# Sheet1.net
KiCad netlist of a schematic drawn in Altium Designer
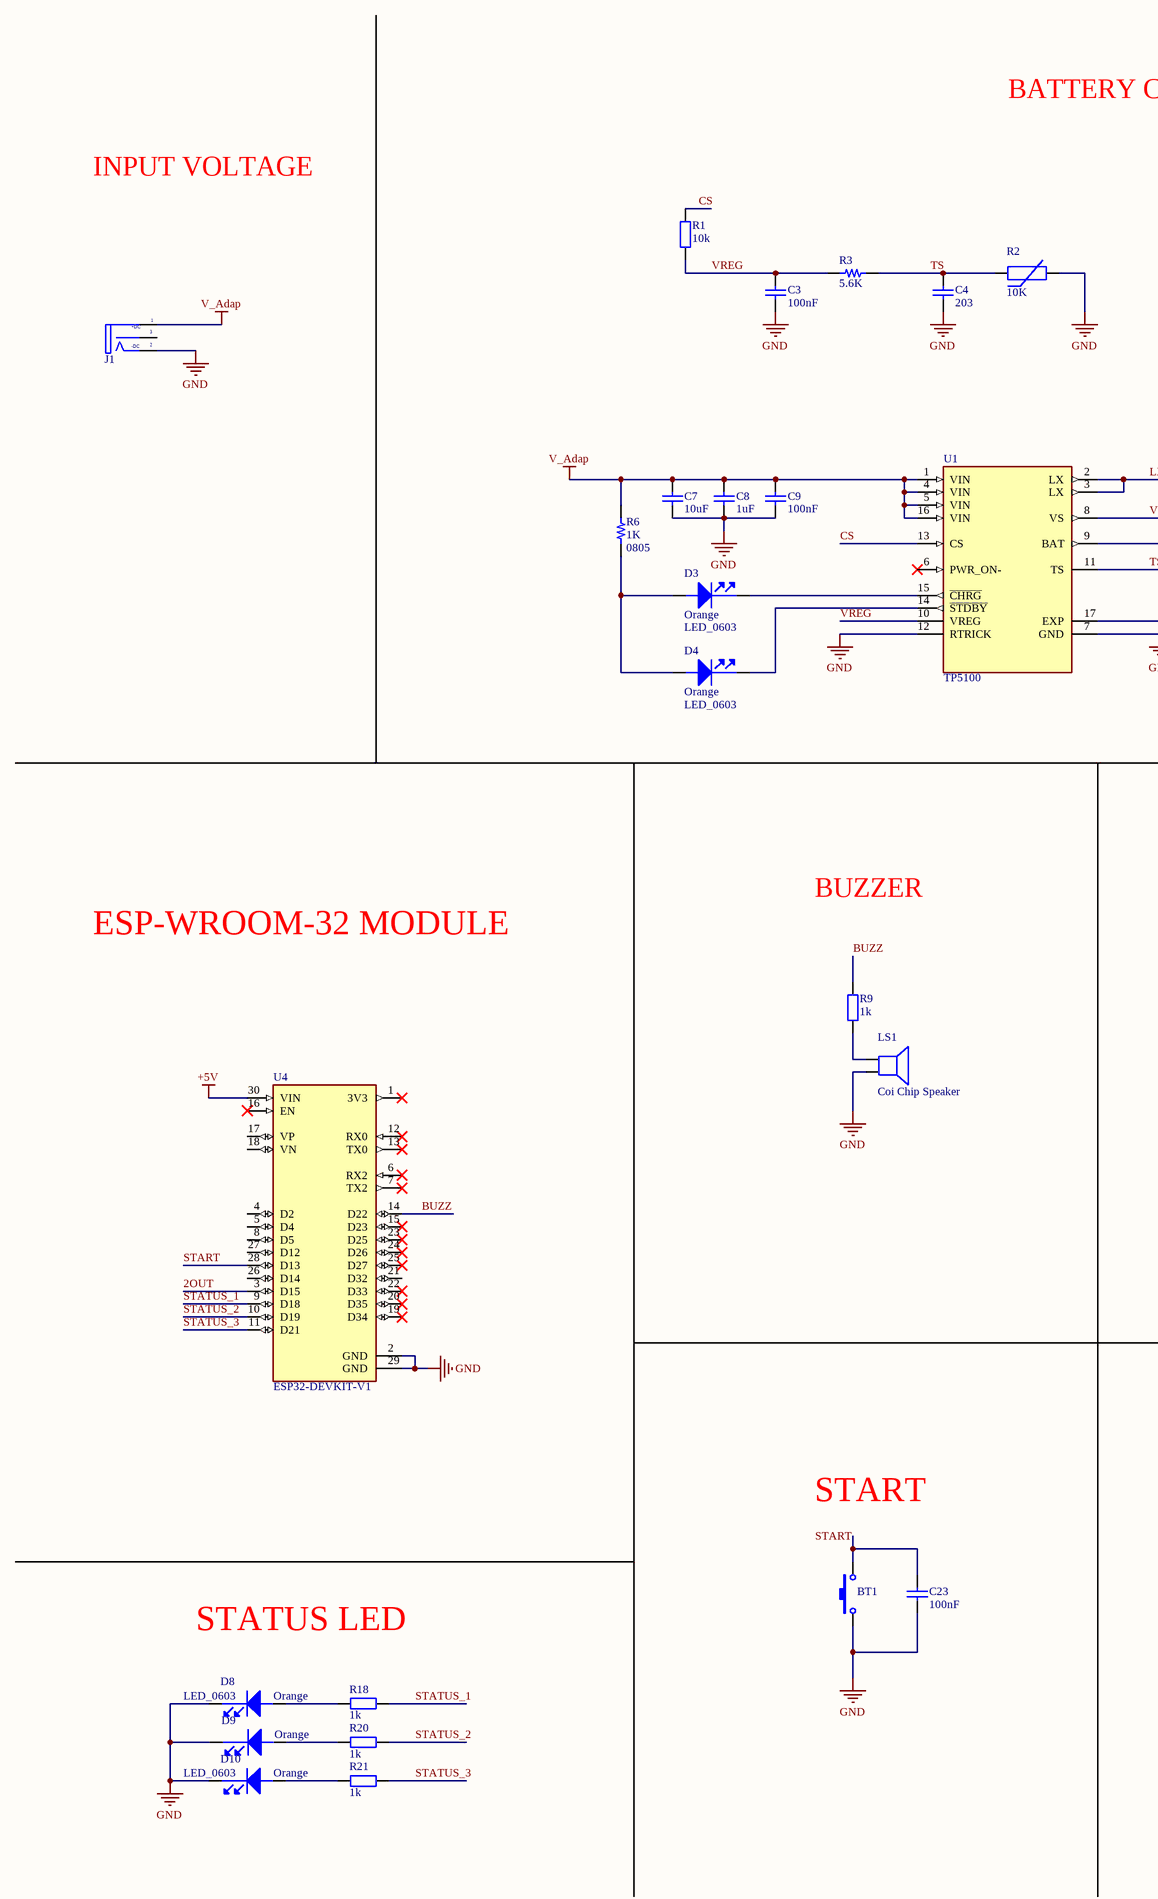
[diagram p0: Sheet1.SchDoc, left]
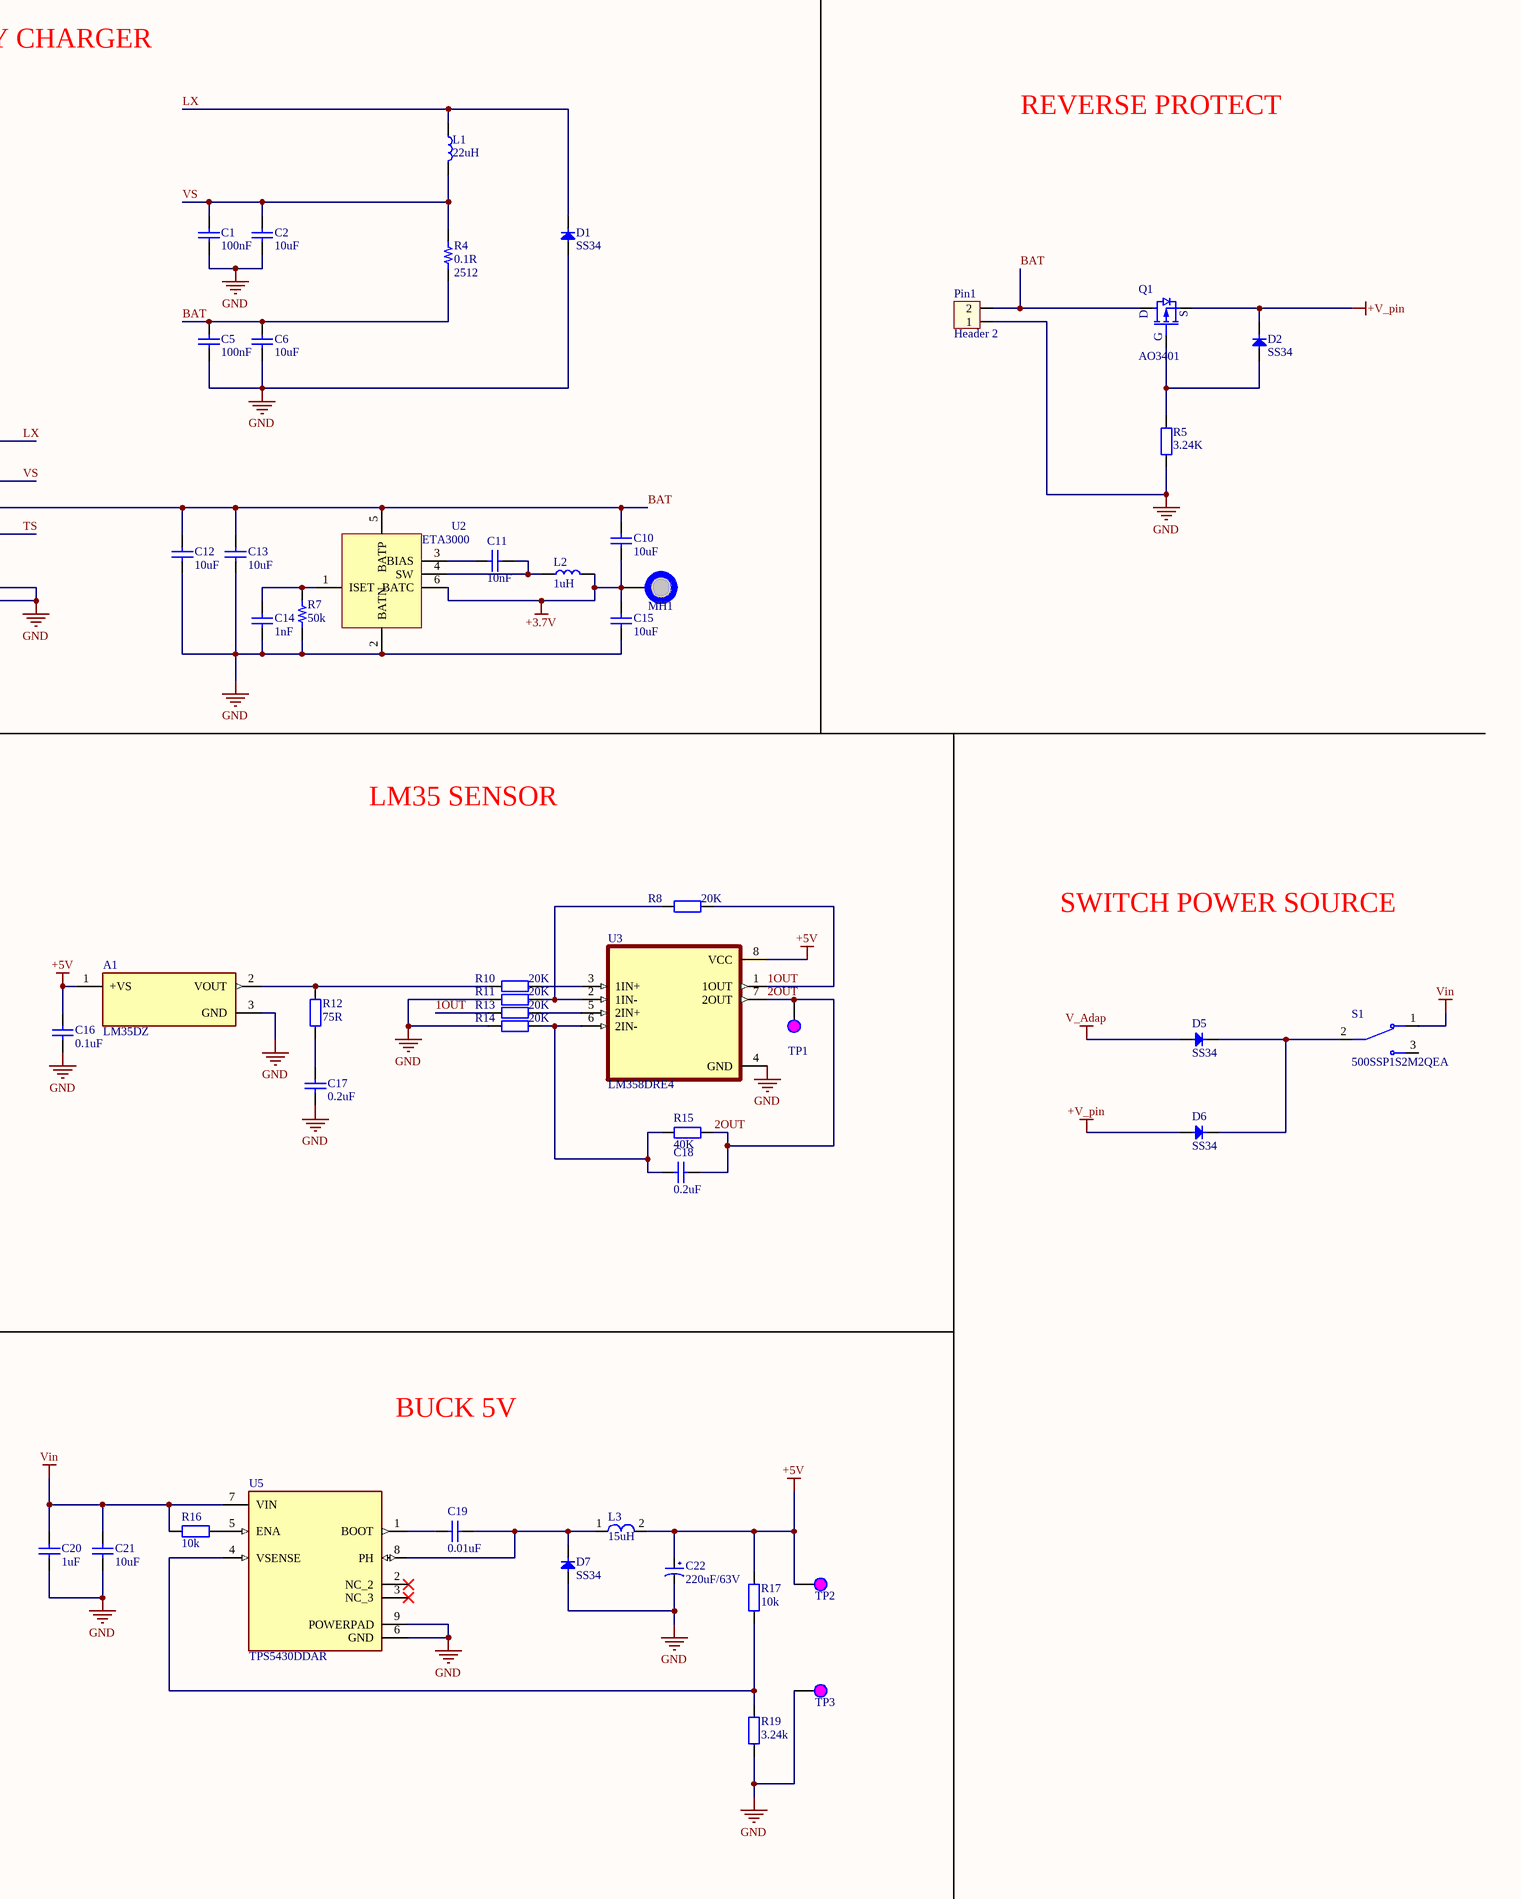
[diagram p1: Sheet1.SchDoc, right]

(export (version "E")
  (design (tool "Eeschema 10.0.6"))
  (components
    (comp (ref "A1")
      (value "LM35DZ")
      (footprint "TO92127P521H735-3")
      (description "Temperature Sensor Analog, Local 0Â°C ~ 100Â°C 10mV/Â°C TO-92-3")
      (fields (field (name "MF") "Texas Instruments"))
      (libsource (lib "LM35DZ_NOPB") (part "LM35DZ/NOPB"))
    )
    (comp (ref "BT1")
      (value "Nut Nhan 2 Chan SMD 3x6x2.5")
      (footprint "Nut Nhan 2 Chan SMD 3x6x2.5")
      (libsource (lib "Altium_Lib_by_KhueNguyenCreator") (part "Nut Nhan 2 Chan SMD 3x6x2.5"))
    )
    (comp (ref "C1")
      (value "100nF")
      (footprint "C0603C/1608MM")
      (description "Cap Ceramic 0.1uF 16V X7R 5% SMD 0603 125C T/R")
      (fields
        (field (name "MANUFACTURER") "Yageo")
        (field (name "MANUFACTURER PART NUMBER") "CC0603JRX7R7BB104")
      )
      (libsource (lib "Howard") (part "CAP CER 100nF 16V 5% X7R 0603"))
    )
    (comp (ref "C2")
      (value "10uF")
      (footprint "C0603C/1608MM")
      (description "CAP CER 0603 10uF 16V X7R 10%")
      (libsource (lib "Howard") (part "CAP CER 10uF 16V X7R 0603"))
    )
    (comp (ref "C3")
      (value "100nF")
      (footprint "C0603C/1608MM")
      (description "Cap Ceramic 0.1uF 16V X7R 5% SMD 0603 125C T/R")
      (fields
        (field (name "MANUFACTURER") "Yageo")
        (field (name "MANUFACTURER PART NUMBER") "CC0603JRX7R7BB104")
      )
      (libsource (lib "Howard") (part "CAP CER 100nF 16V 5% X7R 0603"))
    )
    (comp (ref "C4")
      (value "203")
      (footprint "tu gom")
      (description "Cắm")
      (libsource (lib "Altium_Lib_by_KhueNguyenCreator") (part "Tu gom 203 50V"))
    )
    (comp (ref "C5")
      (value "100nF")
      (footprint "C0603C/1608MM")
      (description "Cap Ceramic 0.1uF 16V X7R 5% SMD 0603 125C T/R")
      (fields
        (field (name "MANUFACTURER") "Yageo")
        (field (name "MANUFACTURER PART NUMBER") "CC0603JRX7R7BB104")
      )
      (libsource (lib "Howard") (part "CAP CER 100nF 16V 5% X7R 0603"))
    )
    (comp (ref "C6")
      (value "10uF")
      (footprint "C0603C/1608MM")
      (description "CAP CER 0603 10uF 16V X7R 10%")
      (libsource (lib "Howard") (part "CAP CER 10uF 16V X7R 0603"))
    )
    (comp (ref "C7")
      (value "10uF")
      (footprint "C0603C/1608MM")
      (description "CAP CER 0603 10uF 16V X7R 10%")
      (libsource (lib "Howard") (part "CAP CER 10uF 16V X7R 0603"))
    )
    (comp (ref "C8")
      (value "1uF")
      (footprint "C0603C/1608MM")
      (description "CAP CER 0603 10uF 16V X7R 10%")
      (libsource (lib "Howard") (part "CAP CER 10uF 16V X7R 0603"))
    )
    (comp (ref "C9")
      (value "100nF")
      (footprint "C0603C/1608MM")
      (description "Cap Ceramic 0.1uF 16V X7R 5% SMD 0603 125C T/R")
      (fields
        (field (name "MANUFACTURER") "Yageo")
        (field (name "MANUFACTURER PART NUMBER") "CC0603JRX7R7BB104")
      )
      (libsource (lib "Howard") (part "CAP CER 100nF 16V 5% X7R 0603"))
    )
    (comp (ref "C10")
      (value "10uF")
      (footprint "C0603C/1608MM")
      (description "CAP CER 0603 10uF 16V X7R 10%")
      (libsource (lib "Howard") (part "CAP CER 10uF 16V X7R 0603"))
    )
    (comp (ref "C11")
      (value "10nF")
      (footprint "C0603C/1608MM")
      (description "CAP CER 0603 10NF 16V X7R 10%")
      (fields
        (field (name "MANUFACTURER") "KEMET")
        (field (name "MANUFACTURER PART NUMBER") "C0603C103K4RECAUTO")
      )
      (libsource (lib "Howard") (part "CAP CER 10nF 16V X7R 0603"))
    )
    (comp (ref "C12")
      (value "10uF")
      (footprint "C0603C/1608MM")
      (description "CAP CER 0603 10uF 16V X7R 10%")
      (libsource (lib "Howard") (part "CAP CER 10uF 16V X7R 0603"))
    )
    (comp (ref "C13")
      (value "10uF")
      (footprint "C0603C/1608MM")
      (description "CAP CER 0603 10uF 16V X7R 10%")
      (libsource (lib "Howard") (part "CAP CER 10uF 16V X7R 0603"))
    )
    (comp (ref "C14")
      (value "1nF")
      (footprint "C0603C/1608MM")
      (description "1000 pF ±5% 16V Ceramic Capacitor X7R 0603 (1608 Metric)")
      (fields
        (field (name "MANUFACTURER") "KEMET")
        (field (name "MANUFACTURER PART NUMBER") "C0603X102J4RECAUTO")
      )
      (libsource (lib "Howard") (part "CAP CER 1nF 16V 5% X7R 0603"))
    )
    (comp (ref "C15")
      (value "10uF")
      (footprint "C0603C/1608MM")
      (description "CAP CER 0603 10uF 16V X7R 10%")
      (libsource (lib "Howard") (part "CAP CER 10uF 16V X7R 0603"))
    )
    (comp (ref "C16")
      (value "0.1uF")
      (footprint "tu 0805")
      (description "Dán")
      (libsource (lib "Tu dien") (part "Tu 0805 10pF 50V 10%"))
    )
    (comp (ref "C17")
      (value "0.2uF")
      (footprint "tu 0805")
      (description "Dán")
      (libsource (lib "Tu dien") (part "Tu 0805 10pF 50V 10%"))
    )
    (comp (ref "C18")
      (value "0.2uF")
      (footprint "tu 0805")
      (description "Dán")
      (libsource (lib "Tu dien") (part "Tu 0805 10pF 50V 10%"))
    )
    (comp (ref "C19")
      (value "0.01uF")
      (footprint "tu 0805")
      (description "Dán")
      (libsource (lib "Tu dien") (part "Tu 0805 10pF 50V 10%"))
    )
    (comp (ref "C20")
      (value "1uF")
      (footprint "tu 0805")
      (description "Dán")
      (libsource (lib "Tu dien") (part "Tu 0805 10pF 50V 10%"))
    )
    (comp (ref "C21")
      (value "10uF")
      (footprint "tu 0805")
      (description "Dán")
      (libsource (lib "Tu dien") (part "Tu 0805 10pF 50V 10%"))
    )
    (comp (ref "C22")
      (value "220uF/63V")
      (footprint "CAP_ALUM_D070_S35_H115")
      (description "Cap Aluminum 47uF 63V 20% (8 X 11.5mm) Radial 3.5mm 405mA 3000 hr 105C Ammo Pack")
      (fields
        (field (name "MANUFACTURER") "Nichicon")
        (field (name "MANUFACTURER PART NUMBER") "UPW1J470MPD1TD")
      )
      (libsource (lib "Howard") (part "CAP ALUM 47UF 20% 63V RADIAL"))
    )
    (comp (ref "C23")
      (value "100nF")
      (footprint "C0603C/1608MM")
      (description "Cap Ceramic 0.1uF 16V X7R 5% SMD 0603 125C T/R")
      (fields
        (field (name "MANUFACTURER") "Yageo")
        (field (name "MANUFACTURER PART NUMBER") "CC0603JRX7R7BB104")
      )
      (libsource (lib "Howard") (part "CAP CER 100nF 16V 5% X7R 0603"))
    )
    (comp (ref "D1")
      (value "SS34")
      (footprint "SMA (DO-214AC)")
      (description "SS Series 500 mV 3 A 40 V Max Reverse Voltage Schottky Rectifier - DO-214AB")
      (fields (field (name "MANUFACTURER") "Taiwan Semiconductor"))
      (libsource (lib "Howard") (part "DIODE SCHOTTKY 40V 3A SMC"))
    )
    (comp (ref "D2")
      (value "SS34")
      (footprint "SMA (DO-214AC)")
      (description "SS Series 500 mV 3 A 40 V Max Reverse Voltage Schottky Rectifier - DO-214AB")
      (fields (field (name "MANUFACTURER") "Taiwan Semiconductor"))
      (libsource (lib "Howard") (part "DIODE SCHOTTKY 40V 3A SMC"))
    )
    (comp (ref "D3")
      (value "Orange")
      (footprint "LED_0603_0m65")
      (description "LED SMARTLED ORANGE 606NM 0603")
      (fields
        (field (name "MANUFACTURER") "OSRAM Opto Semiconductors Inc")
        (field (name "MANUFACTURER PART NUMBER") "LO L29K-H2K1-24-Z")
        (field (name "PACKAGE / CASE") "LED_0603")
        (field (name "BY") "Hieu.Nguyen_20191030")
      )
      (libsource (lib "Howard") (part "LED ORANGE 606NM 0603"))
    )
    (comp (ref "D4")
      (value "Orange")
      (footprint "LED_0603_0m65")
      (description "LED SMARTLED ORANGE 606NM 0603")
      (fields
        (field (name "MANUFACTURER") "OSRAM Opto Semiconductors Inc")
        (field (name "MANUFACTURER PART NUMBER") "LO L29K-H2K1-24-Z")
        (field (name "PACKAGE / CASE") "LED_0603")
        (field (name "BY") "Hieu.Nguyen_20191030")
      )
      (libsource (lib "Howard") (part "LED ORANGE 606NM 0603"))
    )
    (comp (ref "D5")
      (value "SS34")
      (footprint "SMA (DO-214AC)")
      (description "SS Series 500 mV 3 A 40 V Max Reverse Voltage Schottky Rectifier - DO-214AB")
      (fields (field (name "MANUFACTURER") "Taiwan Semiconductor"))
      (libsource (lib "Howard") (part "DIODE SCHOTTKY 40V 3A SMC"))
    )
    (comp (ref "D6")
      (value "SS34")
      (footprint "SMA (DO-214AC)")
      (description "SS Series 500 mV 3 A 40 V Max Reverse Voltage Schottky Rectifier - DO-214AB")
      (fields (field (name "MANUFACTURER") "Taiwan Semiconductor"))
      (libsource (lib "Howard") (part "DIODE SCHOTTKY 40V 3A SMC"))
    )
    (comp (ref "D7")
      (value "SS34")
      (footprint "SMA (DO-214AC)")
      (description "SS Series 500 mV 3 A 40 V Max Reverse Voltage Schottky Rectifier - DO-214AB")
      (fields (field (name "MANUFACTURER") "Taiwan Semiconductor"))
      (libsource (lib "Howard") (part "DIODE SCHOTTKY 40V 3A SMC"))
    )
    (comp (ref "D8")
      (value "Orange")
      (footprint "LED_0603_0m65")
      (description "LED SMARTLED ORANGE 606NM 0603")
      (fields
        (field (name "MANUFACTURER") "OSRAM Opto Semiconductors Inc")
        (field (name "MANUFACTURER PART NUMBER") "LO L29K-H2K1-24-Z")
        (field (name "PACKAGE / CASE") "LED_0603")
        (field (name "BY") "Hieu.Nguyen_20191030")
      )
      (libsource (lib "Howard") (part "LED ORANGE 606NM 0603"))
    )
    (comp (ref "D9")
      (value "Orange")
      (footprint "LED_0603_0m65")
      (description "LED SMARTLED ORANGE 606NM 0603")
      (fields
        (field (name "MANUFACTURER") "OSRAM Opto Semiconductors Inc")
        (field (name "MANUFACTURER PART NUMBER") "LO L29K-H2K1-24-Z")
        (field (name "BY") "Hieu.Nguyen_20191030")
      )
      (libsource (lib "Howard") (part "LED ORANGE 606NM 0603"))
    )
    (comp (ref "D10")
      (value "Orange")
      (footprint "LED_0603_0m65")
      (description "LED SMARTLED ORANGE 606NM 0603")
      (fields
        (field (name "MANUFACTURER") "OSRAM Opto Semiconductors Inc")
        (field (name "MANUFACTURER PART NUMBER") "LO L29K-H2K1-24-Z")
        (field (name "PACKAGE / CASE") "LED_0603")
        (field (name "BY") "Hieu.Nguyen_20191030")
      )
      (libsource (lib "Howard") (part "LED ORANGE 606NM 0603"))
    )
    (comp (ref "J1")
      (value "DCIN")
      (footprint "DC0_SMD")
      (description "CONN POWER JACK 2.1X5.5MM SMD")
      (libsource (lib "Howard") (part "DCIN"))
    )
    (comp (ref "L1")
      (value "22uH")
      (footprint "IND 22uH")
      (description "Inductor Power Shielded Wirewound 22uH 20% 100KHz Ferrite 3A 0.05Ohm DCR Automotive T/R")
      (fields
        (field (name "MANUFACTURER") "Wurth Electronics")
        (field (name "MANUFACTURER PART NUMBER") "7447714220")
      )
      (libsource (lib "Howard") (part "IND FIXED 22UH 3A 50 MOHM SMD CD104-220 10x10x4mm"))
    )
    (comp (ref "L2")
      (value "1uH")
      (footprint "IND 22uH")
      (description "Inductor Power Shielded Wirewound 22uH 20% 100KHz Ferrite 3A 0.05Ohm DCR Automotive T/R")
      (fields
        (field (name "MANUFACTURER") "Wurth Electronics")
        (field (name "MANUFACTURER PART NUMBER") "7447714220")
      )
      (libsource (lib "Howard") (part "IND FIXED 22UH 3A 50 MOHM SMD CD104-220 10x10x4mm"))
    )
    (comp (ref "L3")
      (value "15uH")
      (footprint "L-SMD-M-7.3x4.5")
      (fields
        (field (name "PARTNO") "78477010")
        (field (name "MANUFACTURER") "Wurth Elektronik")
        (field (name "CREATED BY") "Baojun Chen")
      )
      (libsource (lib "My Library") (part "L-SMD-1"))
    )
    (comp (ref "LS1")
      (value "Coi Chip Speaker")
      (footprint "Coi Chip Speacker")
      (description "Còi chip")
      (libsource (lib "Altium_Lib_by_KhueNguyenCreator") (part "Coi Chip Speaker"))
    )
    (comp (ref "MH1")
      (value "MH_3MMD_1.5MMH")
      (footprint "MH_3MMD_1.5MMH")
      (description "Mounting Hole 3mm Diameter, 1.5mm Hole")
      (libsource (lib "Howard") (part "MH_3MMD_1.5MMH"))
    )
    (comp (ref "Pin1")
      (value "Header 2")
      (footprint "HED2")
      (description "Header 2 (Green)")
      (libsource (lib "My Library") (part "Hed2"))
    )
    (comp (ref "Q1")
      (value "AO3401")
      (footprint "SOT 23")
      (description "Transistor P-Channel MOSFET; 30V; 4, 2A; 1, 4W; 85 mOhm; -55°C ~ 150°C; ;")
      (fields
        (field (name "MANUFACTURER") "Alpha & Omega Semiconductor")
        (field (name "MANUFACTURER PART NUMBER") "AO3401A")
      )
      (libsource (lib "Howard") (part "MOSFET P-CH 30V 4A SOT23-3"))
    )
    (comp (ref "R1")
      (value "10k")
      (footprint "tro smd 0603")
      (description "Dán")
      (libsource (lib "Altium_Lib_by_KhueNguyenCreator") (part "Tro 0603 5% 10k"))
    )
    (comp (ref "R2")
      (value "10K")
      (footprint "RESC-0603 (1608)")
      (description "THERMISTOR 10K OHM 1% 0603")
      (fields (field (name "MPN") "NTCG163JF103FT1"))
      (libsource (lib "BYTECH_HW_LIB_2019") (part "NTCG163JF103FT1"))
    )
    (comp (ref "R3")
      (value "5.6K")
      (footprint "R0603B/1608MM")
      (description "Surface Mount Thick Film Resistor, RC Series, 10 kohm, 100 mW, - 5%, 50 V, 0603 [1608 Metric]")
      (fields
        (field (name "MANUFACTURER") "Yageo")
        (field (name "MANUFACTURER PART NUMBER") "RC0603JR-0710KL")
      )
      (libsource (lib "Howard") (part "RES SMD 10K OHM 5% 1/10W 0603"))
    )
    (comp (ref "R4")
      (value "0.1R")
      (footprint "R2512B/6332MM")
      (description "Surface Mount Thick Film Resistor, RC Series, 10 kohm, 1W, - 5%, 50 V, 2512")
      (fields
        (field (name "MANUFACTURER") "Yageo")
        (field (name "MANUFACTURER PART NUMBER") "RC0603JR-0710KL")
        (field (name "CASE/PACKAGE") "2512")
      )
      (libsource (lib "Howard") (part "RES SMD 0.2 OHM 5% 1W 2512"))
    )
    (comp (ref "R5")
      (value "3.24K")
      (footprint "tro smd 0805")
      (description "Dán")
      (libsource (lib "Dien Tro") (part "Tro 0805 5% 560R"))
    )
    (comp (ref "R6")
      (value "1K")
      (footprint "R0805B/2012MM")
      (description "Res Thick Film 0805 1.8M Ohm 5% 1/8W ±100ppm/°C Molded SMD SMD Paper T/R")
      (fields
        (field (name "MANUFACTURER") "Yageo")
        (field (name "MANUFACTURER PART NUMBER") "RC0805JR-071M8L")
        (field (name "CASE/PACKAGE") "0805")
      )
      (libsource (lib "Howard") (part "RES SMD 1.8M OHM 5% 1/8W 0805"))
    )
    (comp (ref "R7")
      (value "50k")
      (footprint "R0603B/1608MM")
      (description "Surface Mount Thick Film Resistor, RC Series, 10 kohm, 100 mW, - 5%, 50 V, 0603 [1608 Metric]")
      (fields
        (field (name "MANUFACTURER") "Yageo")
        (field (name "MANUFACTURER PART NUMBER") "RC0603JR-0710KL")
      )
      (libsource (lib "Howard") (part "RES SMD 10K OHM 5% 1/10W 0603"))
    )
    (comp (ref "R8")
      (value "20K")
      (footprint "tro smd 0805")
      (description "Dán")
      (libsource (lib "Dien Tro") (part "Tro 0805 5% 3.3k"))
    )
    (comp (ref "R9")
      (value "1k")
      (footprint "tro smd 0603")
      (description "Dán")
      (libsource (lib "Altium_Lib_by_KhueNguyenCreator") (part "Tro 0603 1% 1k"))
    )
    (comp (ref "R10")
      (value "20K")
      (footprint "tro smd 0805")
      (description "Dán")
      (libsource (lib "Dien Tro") (part "Tro 0805 5% 3.3k"))
    )
    (comp (ref "R11")
      (value "20K")
      (footprint "tro smd 0805")
      (description "Dán")
      (libsource (lib "Dien Tro") (part "Tro 0805 5% 3.3k"))
    )
    (comp (ref "R12")
      (value "75R")
      (footprint "tro smd 0805")
      (description "Dán")
      (libsource (lib "Dien Tro") (part "Tro 0805 5% 3.3k"))
    )
    (comp (ref "R13")
      (value "20K")
      (footprint "tro smd 0805")
      (description "Dán")
      (libsource (lib "Dien Tro") (part "Tro 0805 5% 3.3k"))
    )
    (comp (ref "R14")
      (value "20K")
      (footprint "tro smd 0805")
      (description "Dán")
      (libsource (lib "Dien Tro") (part "Tro 0805 5% 3.3k"))
    )
    (comp (ref "R15")
      (value "40K")
      (footprint "tro smd 0805")
      (description "Dán")
      (libsource (lib "Dien Tro") (part "Tro 0805 5% 3.3k"))
    )
    (comp (ref "R16")
      (value "10k")
      (footprint "tro smd 0805")
      (description "Dán")
      (libsource (lib "Dien Tro") (part "Tro 0805 5% 10k"))
    )
    (comp (ref "R17")
      (value "10k")
      (footprint "tro smd 0805")
      (description "Dán")
      (libsource (lib "Dien Tro") (part "Tro 0805 5% 10k"))
    )
    (comp (ref "R18")
      (value "1k")
      (footprint "tro smd 0603")
      (description "Dán")
      (libsource (lib "Altium_Lib_by_KhueNguyenCreator") (part "Tro 0603 1% 1k"))
    )
    (comp (ref "R19")
      (value "3.24k")
      (footprint "tro smd 0805")
      (description "Dán")
      (libsource (lib "Dien Tro") (part "Tro 0805 5% 3.3k"))
    )
    (comp (ref "R20")
      (value "1k")
      (footprint "tro smd 0603")
      (description "Dán")
      (libsource (lib "Altium_Lib_by_KhueNguyenCreator") (part "Tro 0603 1% 1k"))
    )
    (comp (ref "R21")
      (value "1k")
      (footprint "tro smd 0603")
      (description "Dán")
      (libsource (lib "Altium_Lib_by_KhueNguyenCreator") (part "Tro 0603 1% 1k"))
    )
    (comp (ref "S1")
      (value "500SSP1S2M2QEA")
      (footprint "SW_500SSP1S2M2QEA")
      (description "Slide Switch SPDT Through Hole")
      (libsource (lib "Howard") (part "500SSP1S2M2QEA"))
    )
    (comp (ref "TP1")
      (value "Testpoint 2")
      (footprint "TP - 2")
      (libsource (lib "My Library") (part "Testpoint 2"))
    )
    (comp (ref "TP2") (value "Testpoint 2") (footprint "TP - 2") (libsource (lib "") (part "Testpoint 2_1")))
    (comp (ref "TP3") (value "Testpoint 2") (footprint "TP - 2") (libsource (lib "") (part "Testpoint 2_1")))
    (comp (ref "U1")
      (value "TP5100")
      (footprint "QFN65P400X400X90-17N")
      (description "2A-switch buck 8.4V / 4.2V rechargeable lithium battery")
      (fields (field (name "MF") "NanJing Top Power ASIC Corp."))
      (libsource (lib "PowerspIOT_1") (part "TP5100"))
    )
    (comp (ref "U2") (value "ETA3000") (footprint "ETA300") (libsource (lib "PowerspIOT") (part "ETA3000")))
    (comp (ref "U3")
      (value "LM358DRE4")
      (footprint "SOIC127P599X175-8N")
      (description "Dual standard operational amplifier 8-SOIC 0 to 70")
      (fields (field (name "MF") "Texas Instruments"))
      (libsource (lib "LM358DRE4") (part "LM358DRE4"))
    )
    (comp (ref "U4")
      (value "ESP32-DEVKIT-V1")
      (footprint "MODULE_ESP32_DEVKIT_V1")
      (fields (field (name "MF") "Do it"))
      (libsource (lib "ESP32-DEVKIT-V1") (part "ESP32-DEVKIT-V1"))
    )
    (comp (ref "U5")
      (value "TPS5430DDAR")
      (footprint "CONV_TPS5430DDAR")
      (description "5.5V to 36V Input, 3A, 500kHz Step-Down Converter")
      (fields (field (name "MF") "Texas Instruments"))
      (libsource (lib "TPS5430DDAR (1)") (part "TPS5430DDAR"))
    )
  )
  (nets
    (net (code "1") (name "+3.7V") (class "Default")
      (node (ref "C10") (pin "1") (pinfunction "1_1") (pintype "passive"))
      (node (ref "C15") (pin "2") (pinfunction "2_2") (pintype "passive"))
      (node (ref "L2") (pin "2") (pinfunction "2_2") (pintype "passive"))
      (node (ref "MH1") (pin "1") (pinfunction "1_1") (pintype "passive"))
      (node (ref "U2") (pin "6") (pinfunction "BATC_6") (pintype "passive"))
    )
    (net (code "2") (name "+5V") (class "Default")
      (node (ref "A1") (pin "1") (pinfunction "+VS_1") (pintype "power_in"))
      (node (ref "C16") (pin "1") (pinfunction "1_1") (pintype "passive"))
      (node (ref "C22") (pin "1") (pinfunction "1_1") (pintype "passive"))
      (node (ref "L3") (pin "2") (pinfunction "2_2") (pintype "passive"))
      (node (ref "R17") (pin "2") (pinfunction "2_2") (pintype "passive"))
      (node (ref "TP2") (pin "1") (pinfunction "1_1") (pintype "passive"))
      (node (ref "U3") (pin "8") (pinfunction "VCC_8") (pintype "power_in"))
      (node (ref "U4") (pin "30") (pinfunction "VIN_30") (pintype "input"))
    )
    (net (code "3") (name "+V_pin") (class "Default")
      (node (ref "D2") (pin "2") (pinfunction "K_2") (pintype "passive"))
      (node (ref "D6") (pin "1") (pinfunction "A_1") (pintype "passive"))
      (node (ref "Q1") (pin "2") (pinfunction "S_2") (pintype "passive"))
    )
    (net (code "4") (name "/1OUT") (class "Default")
      (node (ref "R13") (pin "2") (pinfunction "2_2") (pintype "passive"))
      (node (ref "R8") (pin "1") (pinfunction "1_1") (pintype "passive"))
      (node (ref "U3") (pin "1") (pinfunction "1OUT_1") (pintype "output"))
    )
    (net (code "5") (name "/2OUT") (class "Default")
      (node (ref "C18") (pin "2") (pinfunction "2_2") (pintype "passive"))
      (node (ref "R15") (pin "2") (pinfunction "2_2") (pintype "passive"))
      (node (ref "TP1") (pin "1") (pinfunction "1_1") (pintype "passive"))
      (node (ref "U3") (pin "7") (pinfunction "2OUT_7") (pintype "output"))
      (node (ref "U4") (pin "3") (pinfunction "D15_3") (pintype "bidirectional"))
    )
    (net (code "6") (name "/BAT") (class "Default")
      (node (ref "C10") (pin "2") (pinfunction "2_2") (pintype "passive"))
      (node (ref "C12") (pin "2") (pinfunction "2_2") (pintype "passive"))
      (node (ref "C13") (pin "2") (pinfunction "2_2") (pintype "passive"))
      (node (ref "C5") (pin "2") (pinfunction "2_2") (pintype "passive"))
      (node (ref "C6") (pin "2") (pinfunction "2_2") (pintype "passive"))
      (node (ref "Pin1") (pin "2") (pinfunction "2_2") (pintype "passive"))
      (node (ref "Q1") (pin "3") (pinfunction "D_3") (pintype "passive"))
      (node (ref "R4") (pin "1") (pinfunction "1_1") (pintype "passive"))
      (node (ref "U1") (pin "9") (pinfunction "BAT_9") (pintype "output"))
      (node (ref "U2") (pin "5") (pinfunction "BATP_5") (pintype "passive"))
    )
    (net (code "7") (name "/BUZZ") (class "Default")
      (node (ref "R9") (pin "2") (pinfunction "2_2") (pintype "passive"))
      (node (ref "U4") (pin "14") (pinfunction "D22_14") (pintype "bidirectional"))
    )
    (net (code "8") (name "/CS") (class "Default")
      (node (ref "R1") (pin "2") (pinfunction "2_2") (pintype "passive"))
      (node (ref "U1") (pin "13") (pinfunction "CS_13") (pintype "input"))
    )
    (net (code "9") (name "/LX") (class "Default")
      (node (ref "D1") (pin "2") (pinfunction "K_2") (pintype "passive"))
      (node (ref "L1") (pin "1") (pinfunction "1_1") (pintype "passive"))
      (node (ref "U1") (pin "2") (pinfunction "LX_2") (pintype "output"))
      (node (ref "U1") (pin "3") (pinfunction "LX_3") (pintype "output"))
    )
    (net (code "10") (name "/START") (class "Default")
      (node (ref "BT1") (pin "2") (pinfunction "2_2") (pintype "passive"))
      (node (ref "C23") (pin "2") (pinfunction "2_2") (pintype "passive"))
      (node (ref "U4") (pin "28") (pinfunction "D13_28") (pintype "bidirectional"))
    )
    (net (code "11") (name "/STATUS_1") (class "Default")
      (node (ref "R18") (pin "1") (pinfunction "1_1") (pintype "passive"))
      (node (ref "U4") (pin "9") (pinfunction "D18_9") (pintype "bidirectional"))
    )
    (net (code "12") (name "/STATUS_2") (class "Default")
      (node (ref "R20") (pin "1") (pinfunction "1_1") (pintype "passive"))
      (node (ref "U4") (pin "10") (pinfunction "D19_10") (pintype "bidirectional"))
    )
    (net (code "13") (name "/STATUS_3") (class "Default")
      (node (ref "R21") (pin "1") (pinfunction "1_1") (pintype "passive"))
      (node (ref "U4") (pin "11") (pinfunction "D21_11") (pintype "bidirectional"))
    )
    (net (code "14") (name "/TS") (class "Default")
      (node (ref "C4") (pin "1") (pinfunction "1_1") (pintype "passive"))
      (node (ref "R2") (pin "1") (pinfunction "1_1") (pintype "passive"))
      (node (ref "R3") (pin "1") (pinfunction "1_1") (pintype "passive"))
      (node (ref "U1") (pin "11") (pinfunction "TS_11") (pintype "passive"))
    )
    (net (code "15") (name "/VREG") (class "Default")
      (node (ref "C3") (pin "2") (pinfunction "2_2") (pintype "passive"))
      (node (ref "R1") (pin "1") (pinfunction "1_1") (pintype "passive"))
      (node (ref "R3") (pin "2") (pinfunction "2_2") (pintype "passive"))
      (node (ref "U1") (pin "10") (pinfunction "VREG_10") (pintype "passive"))
    )
    (net (code "16") (name "/VS") (class "Default")
      (node (ref "C1") (pin "2") (pinfunction "2_2") (pintype "passive"))
      (node (ref "C2") (pin "2") (pinfunction "2_2") (pintype "passive"))
      (node (ref "L1") (pin "2") (pinfunction "2_2") (pintype "passive"))
      (node (ref "R4") (pin "2") (pinfunction "2_2") (pintype "passive"))
      (node (ref "U1") (pin "8") (pinfunction "VS_8") (pintype "output"))
    )
    (net (code "17") (name "GND") (class "Default")
      (node (ref "A1") (pin "3") (pinfunction "GND_3") (pintype "power_in"))
      (node (ref "BT1") (pin "1") (pinfunction "1_1") (pintype "passive"))
      (node (ref "C1") (pin "1") (pinfunction "1_1") (pintype "passive"))
      (node (ref "C12") (pin "1") (pinfunction "1_1") (pintype "passive"))
      (node (ref "C13") (pin "1") (pinfunction "1_1") (pintype "passive"))
      (node (ref "C14") (pin "1") (pinfunction "1_1") (pintype "passive"))
      (node (ref "C15") (pin "1") (pinfunction "1_1") (pintype "passive"))
      (node (ref "C16") (pin "2") (pinfunction "2_2") (pintype "passive"))
      (node (ref "C17") (pin "2") (pinfunction "2_2") (pintype "passive"))
      (node (ref "C2") (pin "1") (pinfunction "1_1") (pintype "passive"))
      (node (ref "C20") (pin "2") (pinfunction "2_2") (pintype "passive"))
      (node (ref "C21") (pin "2") (pinfunction "2_2") (pintype "passive"))
      (node (ref "C22") (pin "2") (pinfunction "2_2") (pintype "passive"))
      (node (ref "C23") (pin "1") (pinfunction "1_1") (pintype "passive"))
      (node (ref "C3") (pin "1") (pinfunction "1_1") (pintype "passive"))
      (node (ref "C4") (pin "2") (pinfunction "2_2") (pintype "passive"))
      (node (ref "C5") (pin "1") (pinfunction "1_1") (pintype "passive"))
      (node (ref "C6") (pin "1") (pinfunction "1_1") (pintype "passive"))
      (node (ref "C7") (pin "1") (pinfunction "1_1") (pintype "passive"))
      (node (ref "C8") (pin "1") (pinfunction "1_1") (pintype "passive"))
      (node (ref "C9") (pin "1") (pinfunction "1_1") (pintype "passive"))
      (node (ref "D1") (pin "1") (pinfunction "A_1") (pintype "passive"))
      (node (ref "D10") (pin "2") (pinfunction "cathode_2") (pintype "passive"))
      (node (ref "D7") (pin "1") (pinfunction "A_1") (pintype "passive"))
      (node (ref "D8") (pin "2") (pinfunction "cathode_2") (pintype "passive"))
      (node (ref "D9") (pin "2") (pinfunction "cathode_2") (pintype "passive"))
      (node (ref "J1") (pin "2") (pinfunction "TN_2") (pintype "passive"))
      (node (ref "LS1") (pin "2") (pinfunction "2_2") (pintype "passive"))
      (node (ref "Pin1") (pin "1") (pinfunction "1_1") (pintype "passive"))
      (node (ref "R11") (pin "2") (pinfunction "2_2") (pintype "passive"))
      (node (ref "R14") (pin "2") (pinfunction "2_2") (pintype "passive"))
      (node (ref "R19") (pin "1") (pinfunction "1_1") (pintype "passive"))
      (node (ref "R2") (pin "2") (pinfunction "2_2") (pintype "passive"))
      (node (ref "R5") (pin "1") (pinfunction "1_1") (pintype "passive"))
      (node (ref "R7") (pin "1") (pinfunction "1_1") (pintype "passive"))
      (node (ref "TP3") (pin "1") (pinfunction "1_1") (pintype "passive"))
      (node (ref "U1") (pin "12") (pinfunction "RTRICK_12") (pintype "passive"))
      (node (ref "U1") (pin "17") (pinfunction "EXP_17") (pintype "passive"))
      (node (ref "U1") (pin "7") (pinfunction "GND_7") (pintype "power_in"))
      (node (ref "U2") (pin "2") (pinfunction "BATN_2") (pintype "passive"))
      (node (ref "U3") (pin "4") (pinfunction "GND_4") (pintype "power_in"))
      (node (ref "U4") (pin "2") (pinfunction "GND_2") (pintype "power_in"))
      (node (ref "U4") (pin "29") (pinfunction "GND_29") (pintype "power_in"))
      (node (ref "U5") (pin "6") (pinfunction "GND_6") (pintype "power_in"))
      (node (ref "U5") (pin "9") (pinfunction "POWERPAD_9") (pintype "power_in"))
    )
    (net (code "18") (name "Net-(A1-VOUT)") (class "Default")
      (node (ref "A1") (pin "2") (pinfunction "VOUT_2") (pintype "output"))
      (node (ref "R10") (pin "1") (pinfunction "1_1") (pintype "passive"))
      (node (ref "R12") (pin "2") (pinfunction "2_2") (pintype "passive"))
    )
    (net (code "19") (name "Net-(C17-Pad1)") (class "Default")
      (node (ref "C17") (pin "1") (pinfunction "1_1") (pintype "passive"))
      (node (ref "R12") (pin "1") (pinfunction "1_1") (pintype "passive"))
    )
    (net (code "20") (name "Net-(D2-A)") (class "Default")
      (node (ref "D2") (pin "1") (pinfunction "A_1") (pintype "passive"))
      (node (ref "Q1") (pin "1") (pinfunction "G_1") (pintype "passive"))
      (node (ref "R5") (pin "2") (pinfunction "2_2") (pintype "passive"))
    )
    (net (code "21") (name "Net-(D3-ANODE)") (class "Default")
      (node (ref "D3") (pin "1") (pinfunction "ANODE_1") (pintype "passive"))
      (node (ref "D4") (pin "1") (pinfunction "ANODE_1") (pintype "passive"))
      (node (ref "R6") (pin "1") (pinfunction "1_1") (pintype "passive"))
    )
    (net (code "22") (name "Net-(D3-cathode)") (class "Default")
      (node (ref "D3") (pin "2") (pinfunction "cathode_2") (pintype "passive"))
      (node (ref "U1") (pin "15") (pinfunction "~{CHRG}_15") (pintype "output"))
    )
    (net (code "23") (name "Net-(D4-cathode)") (class "Default")
      (node (ref "D4") (pin "2") (pinfunction "cathode_2") (pintype "passive"))
      (node (ref "U1") (pin "14") (pinfunction "~{STDBY}_14") (pintype "output"))
    )
    (net (code "24") (name "Net-(D5-K)") (class "Default")
      (node (ref "D5") (pin "2") (pinfunction "K_2") (pintype "passive"))
      (node (ref "D6") (pin "2") (pinfunction "K_2") (pintype "passive"))
      (node (ref "S1") (pin "2") (pinfunction "COM_2") (pintype "passive"))
    )
    (net (code "25") (name "Net-(D7-K)") (class "Default")
      (node (ref "C19") (pin "2") (pinfunction "2_2") (pintype "passive"))
      (node (ref "D7") (pin "2") (pinfunction "K_2") (pintype "passive"))
      (node (ref "L3") (pin "1") (pinfunction "1_1") (pintype "passive"))
      (node (ref "U5") (pin "8") (pinfunction "PH_8") (pintype "bidirectional"))
    )
    (net (code "26") (name "Net-(D8-ANODE)") (class "Default")
      (node (ref "D8") (pin "1") (pinfunction "ANODE_1") (pintype "passive"))
      (node (ref "R18") (pin "2") (pinfunction "2_2") (pintype "passive"))
    )
    (net (code "27") (name "Net-(D9-ANODE)") (class "Default")
      (node (ref "D9") (pin "1") (pinfunction "ANODE_1") (pintype "passive"))
      (node (ref "R20") (pin "2") (pinfunction "2_2") (pintype "passive"))
    )
    (net (code "28") (name "Net-(D10-ANODE)") (class "Default")
      (node (ref "D10") (pin "1") (pinfunction "ANODE_1") (pintype "passive"))
      (node (ref "R21") (pin "2") (pinfunction "2_2") (pintype "passive"))
    )
    (net (code "29") (name "Net-(LS1-Pad1)") (class "Default")
      (node (ref "LS1") (pin "1") (pinfunction "1_1") (pintype "passive"))
      (node (ref "R9") (pin "1") (pinfunction "1_1") (pintype "passive"))
    )
    (net (code "30") (name "Net-(U2-BIAS)") (class "Default")
      (node (ref "C11") (pin "1") (pinfunction "1_1") (pintype "passive"))
      (node (ref "U2") (pin "3") (pinfunction "BIAS_3") (pintype "passive"))
    )
    (net (code "31") (name "Net-(U2-ISET)") (class "Default")
      (node (ref "C14") (pin "2") (pinfunction "2_2") (pintype "passive"))
      (node (ref "R7") (pin "2") (pinfunction "2_2") (pintype "passive"))
      (node (ref "U2") (pin "1") (pinfunction "ISET_1") (pintype "passive"))
    )
    (net (code "32") (name "Net-(U2-SW)") (class "Default")
      (node (ref "C11") (pin "2") (pinfunction "2_2") (pintype "passive"))
      (node (ref "L2") (pin "1") (pinfunction "1_1") (pintype "passive"))
      (node (ref "U2") (pin "4") (pinfunction "SW_4") (pintype "passive"))
    )
    (net (code "33") (name "Net-(U3-1IN+)") (class "Default")
      (node (ref "R10") (pin "2") (pinfunction "2_2") (pintype "passive"))
      (node (ref "U3") (pin "3") (pinfunction "1IN+_3") (pintype "input"))
    )
    (net (code "34") (name "Net-(U3-1IN-)") (class "Default")
      (node (ref "R11") (pin "1") (pinfunction "1_1") (pintype "passive"))
      (node (ref "R8") (pin "2") (pinfunction "2_2") (pintype "passive"))
      (node (ref "U3") (pin "2") (pinfunction "1IN-_2") (pintype "input"))
    )
    (net (code "35") (name "Net-(U3-2IN+)") (class "Default")
      (node (ref "R13") (pin "1") (pinfunction "1_1") (pintype "passive"))
      (node (ref "U3") (pin "5") (pinfunction "2IN+_5") (pintype "input"))
    )
    (net (code "36") (name "Net-(U3-2IN-)") (class "Default")
      (node (ref "C18") (pin "1") (pinfunction "1_1") (pintype "passive"))
      (node (ref "R14") (pin "1") (pinfunction "1_1") (pintype "passive"))
      (node (ref "R15") (pin "1") (pinfunction "1_1") (pintype "passive"))
      (node (ref "U3") (pin "6") (pinfunction "2IN-_6") (pintype "input"))
    )
    (net (code "37") (name "Net-(U5-BOOT)") (class "Default")
      (node (ref "C19") (pin "1") (pinfunction "1_1") (pintype "passive"))
      (node (ref "U5") (pin "1") (pinfunction "BOOT_1") (pintype "output"))
    )
    (net (code "38") (name "Net-(U5-ENA)") (class "Default")
      (node (ref "R16") (pin "1") (pinfunction "1_1") (pintype "passive"))
      (node (ref "U5") (pin "5") (pinfunction "ENA_5") (pintype "input"))
    )
    (net (code "39") (name "Net-(U5-VSENSE)") (class "Default")
      (node (ref "R17") (pin "1") (pinfunction "1_1") (pintype "passive"))
      (node (ref "R19") (pin "2") (pinfunction "2_2") (pintype "passive"))
      (node (ref "U5") (pin "4") (pinfunction "VSENSE_4") (pintype "input"))
    )
    (net (code "40") (name "V_Adap") (class "Default")
      (node (ref "C7") (pin "2") (pinfunction "2_2") (pintype "passive"))
      (node (ref "C8") (pin "2") (pinfunction "2_2") (pintype "passive"))
      (node (ref "C9") (pin "2") (pinfunction "2_2") (pintype "passive"))
      (node (ref "D5") (pin "1") (pinfunction "A_1") (pintype "passive"))
      (node (ref "J1") (pin "1") (pinfunction "T_1") (pintype "passive"))
      (node (ref "R6") (pin "2") (pinfunction "2_2") (pintype "passive"))
      (node (ref "U1") (pin "1") (pinfunction "VIN_1") (pintype "input"))
      (node (ref "U1") (pin "16") (pinfunction "VIN_16") (pintype "input"))
      (node (ref "U1") (pin "4") (pinfunction "VIN_4") (pintype "input"))
      (node (ref "U1") (pin "5") (pinfunction "VIN_5") (pintype "input"))
    )
    (net (code "41") (name "Vin") (class "Default")
      (node (ref "C20") (pin "1") (pinfunction "1_1") (pintype "passive"))
      (node (ref "C21") (pin "1") (pinfunction "1_1") (pintype "passive"))
      (node (ref "R16") (pin "2") (pinfunction "2_2") (pintype "passive"))
      (node (ref "S1") (pin "1") (pinfunction "NC_1") (pintype "passive"))
      (node (ref "U5") (pin "7") (pinfunction "VIN_7") (pintype "power_in"))
    )
    (net (code "42") (name "unconnected-(J1-S-Pad3)") (class "Default")
      (node (ref "J1") (pin "3") (pinfunction "S_3") (pintype "power_in"))
    )
    (net (code "43") (name "unconnected-(S1-NO-Pad3)") (class "Default")
      (node (ref "S1") (pin "3") (pinfunction "NO_3") (pintype "passive"))
    )
    (net (code "44") (name "unconnected-(U1-PWR_ON--Pad6)") (class "Default")
      (node (ref "U1") (pin "6") (pinfunction "PWR_ON-_6") (pintype "input+no_connect"))
    )
    (net (code "45") (name "unconnected-(U4-3V3-Pad1)") (class "Default")
      (node (ref "U4") (pin "1") (pinfunction "3V3_1") (pintype "output+no_connect"))
    )
    (net (code "46") (name "unconnected-(U4-D2-Pad4)") (class "Default")
      (node (ref "U4") (pin "4") (pinfunction "D2_4") (pintype "bidirectional"))
    )
    (net (code "47") (name "unconnected-(U4-D4-Pad5)") (class "Default")
      (node (ref "U4") (pin "5") (pinfunction "D4_5") (pintype "bidirectional"))
    )
    (net (code "48") (name "unconnected-(U4-D5-Pad8)") (class "Default")
      (node (ref "U4") (pin "8") (pinfunction "D5_8") (pintype "bidirectional"))
    )
    (net (code "49") (name "unconnected-(U4-D12-Pad27)") (class "Default")
      (node (ref "U4") (pin "27") (pinfunction "D12_27") (pintype "bidirectional"))
    )
    (net (code "50") (name "unconnected-(U4-D14-Pad26)") (class "Default")
      (node (ref "U4") (pin "26") (pinfunction "D14_26") (pintype "bidirectional"))
    )
    (net (code "51") (name "unconnected-(U4-D23-Pad15)") (class "Default")
      (node (ref "U4") (pin "15") (pinfunction "D23_15") (pintype "bidirectional+no_connect"))
    )
    (net (code "52") (name "unconnected-(U4-D25-Pad23)") (class "Default")
      (node (ref "U4") (pin "23") (pinfunction "D25_23") (pintype "bidirectional+no_connect"))
    )
    (net (code "53") (name "unconnected-(U4-D26-Pad24)") (class "Default")
      (node (ref "U4") (pin "24") (pinfunction "D26_24") (pintype "bidirectional+no_connect"))
    )
    (net (code "54") (name "unconnected-(U4-D27-Pad25)") (class "Default")
      (node (ref "U4") (pin "25") (pinfunction "D27_25") (pintype "bidirectional+no_connect"))
    )
    (net (code "55") (name "unconnected-(U4-D32-Pad21)") (class "Default")
      (node (ref "U4") (pin "21") (pinfunction "D32_21") (pintype "bidirectional"))
    )
    (net (code "56") (name "unconnected-(U4-D33-Pad22)") (class "Default")
      (node (ref "U4") (pin "22") (pinfunction "D33_22") (pintype "bidirectional+no_connect"))
    )
    (net (code "57") (name "unconnected-(U4-D34-Pad19)") (class "Default")
      (node (ref "U4") (pin "19") (pinfunction "D34_19") (pintype "bidirectional+no_connect"))
    )
    (net (code "58") (name "unconnected-(U4-D35-Pad20)") (class "Default")
      (node (ref "U4") (pin "20") (pinfunction "D35_20") (pintype "bidirectional+no_connect"))
    )
    (net (code "59") (name "unconnected-(U4-EN-Pad16)") (class "Default")
      (node (ref "U4") (pin "16") (pinfunction "EN_16") (pintype "input+no_connect"))
    )
    (net (code "60") (name "unconnected-(U4-RX0-Pad12)") (class "Default")
      (node (ref "U4") (pin "12") (pinfunction "RX0_12") (pintype "input+no_connect"))
    )
    (net (code "61") (name "unconnected-(U4-RX2-Pad6)") (class "Default")
      (node (ref "U4") (pin "6") (pinfunction "RX2_6") (pintype "input+no_connect"))
    )
    (net (code "62") (name "unconnected-(U4-TX0-Pad13)") (class "Default")
      (node (ref "U4") (pin "13") (pinfunction "TX0_13") (pintype "output+no_connect"))
    )
    (net (code "63") (name "unconnected-(U4-TX2-Pad7)") (class "Default")
      (node (ref "U4") (pin "7") (pinfunction "TX2_7") (pintype "output+no_connect"))
    )
    (net (code "64") (name "unconnected-(U4-VN-Pad18)") (class "Default")
      (node (ref "U4") (pin "18") (pinfunction "VN_18") (pintype "bidirectional"))
    )
    (net (code "65") (name "unconnected-(U4-VP-Pad17)") (class "Default")
      (node (ref "U4") (pin "17") (pinfunction "VP_17") (pintype "bidirectional"))
    )
    (net (code "66") (name "unconnected-(U5-NC_2-Pad2)") (class "Default")
      (node (ref "U5") (pin "2") (pinfunction "NC_2_2") (pintype "passive+no_connect"))
    )
    (net (code "67") (name "unconnected-(U5-NC_3-Pad3)") (class "Default")
      (node (ref "U5") (pin "3") (pinfunction "NC_3_3") (pintype "passive+no_connect"))
    )
  )
)
